# MID_AR0234.net
KiCad netlist of a schematic drawn in Altium Designer
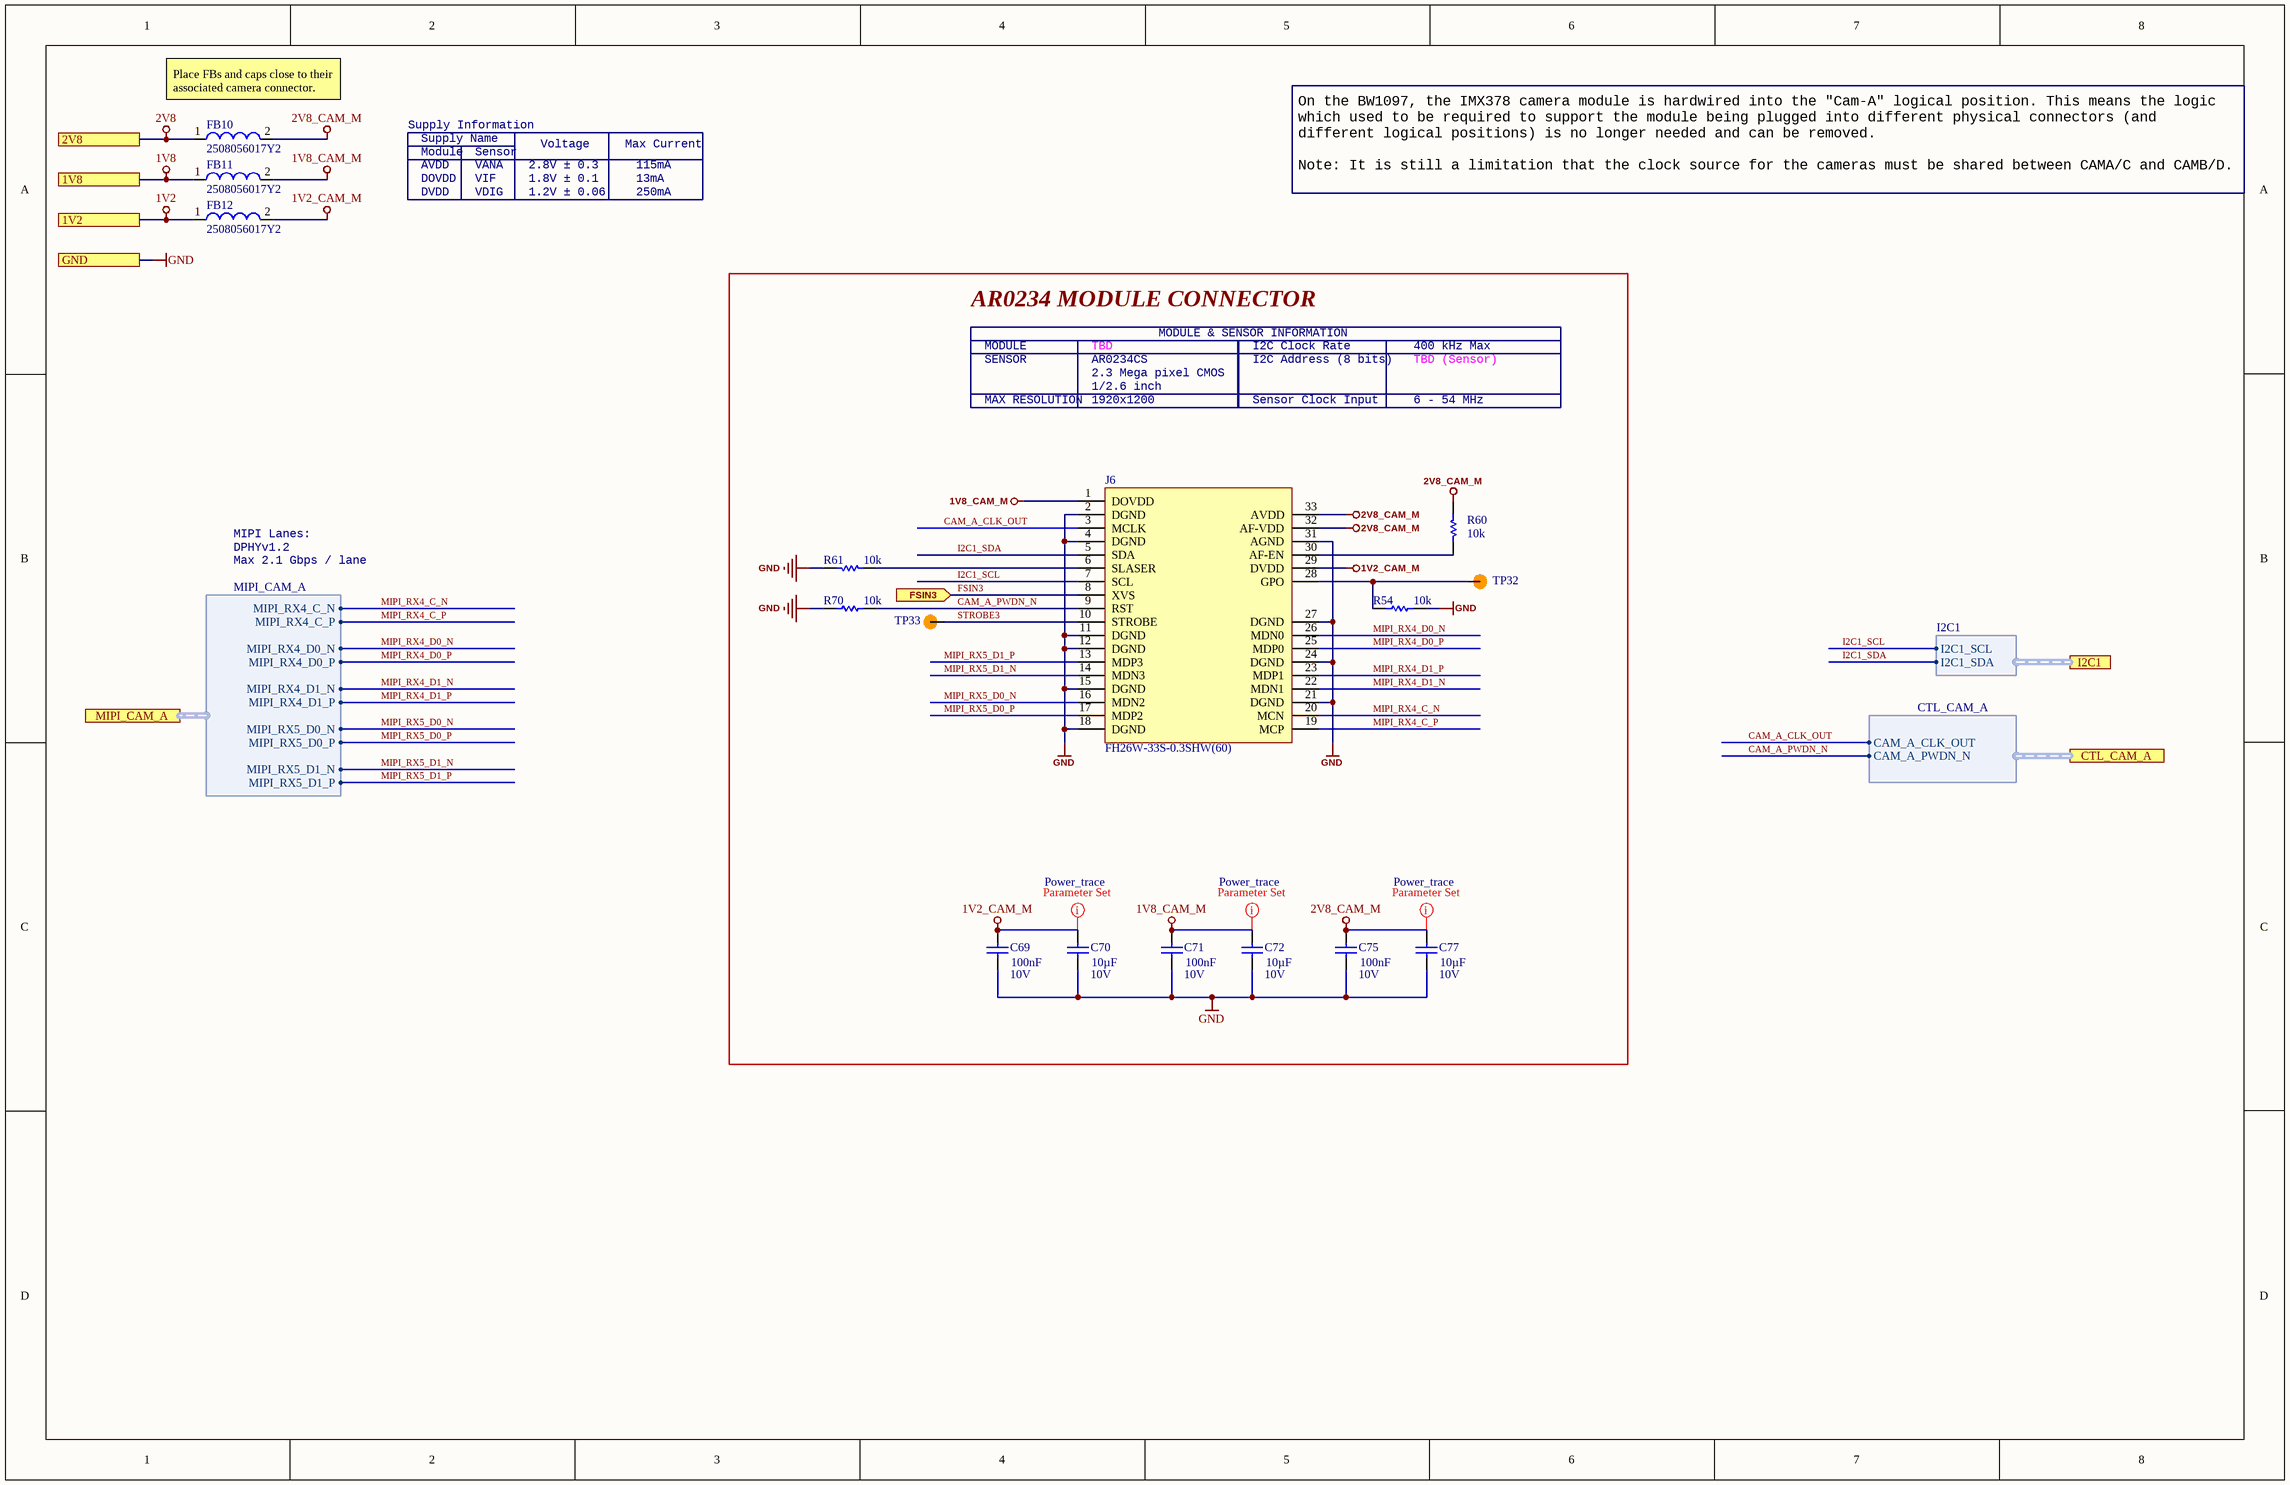
[diagram p0: MID_AR0234.SchDoc]

(export (version "E")
  (design (tool "Eeschema 10.0.6"))
  (components
    (comp (ref "C69")
      (value "100nF")
      (footprint "CAPC0402(1005)70_L")
      (description "CAP CER 0.1UF 10V X7R 0402 5%")
      (fields
        (field (name "TOLERANCE") "5%")
        (field (name "VOLTAGE RATING") "10V")
        (field (name "Comment") "GRM155R71A104JA01D")
      )
      (libsource (lib "Luxonis LLC") (part "GRM188R61C475KAAJD"))
    )
    (comp (ref "C70")
      (value "10µF")
      (footprint "CAPC0603(1608)100_L")
      (description "CAP CER 10UF 10V X5R 0603 20%")
      (fields
        (field (name "TOLERANCE") "20%")
        (field (name "VOLTAGE RATING") "10V")
        (field (name "Comment") "GRM188R61A106ME69D")
      )
      (libsource (lib "Luxonis LLC") (part "LLL153C70G474ME17E"))
    )
    (comp (ref "C71")
      (value "100nF")
      (footprint "CAPC0402(1005)70_L")
      (description "CAP CER 0.1UF 10V X7R 0402 5%")
      (fields
        (field (name "TOLERANCE") "5%")
        (field (name "VOLTAGE RATING") "10V")
        (field (name "Comment") "GRM155R71A104JA01D")
      )
      (libsource (lib "Luxonis LLC") (part "GRM188R61C475KAAJD"))
    )
    (comp (ref "C72")
      (value "10µF")
      (footprint "CAPC0603(1608)100_L")
      (description "CAP CER 10UF 10V X5R 0603 20%")
      (fields
        (field (name "TOLERANCE") "20%")
        (field (name "VOLTAGE RATING") "10V")
        (field (name "Comment") "GRM188R61A106ME69D")
      )
      (libsource (lib "Luxonis LLC") (part "LLL153C70G474ME17E"))
    )
    (comp (ref "C75")
      (value "100nF")
      (footprint "CAPC0402(1005)70_L")
      (description "CAP CER 0.1UF 10V X7R 0402 5%")
      (fields
        (field (name "TOLERANCE") "5%")
        (field (name "VOLTAGE RATING") "10V")
        (field (name "Comment") "GRM155R71A104JA01D")
      )
      (libsource (lib "Luxonis LLC") (part "GRM188R61C475KAAJD"))
    )
    (comp (ref "C77")
      (value "10µF")
      (footprint "CAPC0603(1608)100_L")
      (description "CAP CER 10UF 10V X5R 0603 20%")
      (fields
        (field (name "TOLERANCE") "20%")
        (field (name "VOLTAGE RATING") "10V")
        (field (name "Comment") "GRM188R61A106ME69D")
      )
      (libsource (lib "Luxonis LLC") (part "LLL153C70G474ME17E"))
    )
    (comp (ref "FB10")
      (value "2508056017Y2")
      (footprint "2508056017Y2")
      (description "FERRITE BEAD, 0.1OHM, 2A, 0805, 600R/100MHz")
      (fields (field (name "TOLERANCE") "25%"))
      (libsource (lib "Luxonis LLC") (part "2508056017Y2"))
    )
    (comp (ref "FB11")
      (value "2508056017Y2")
      (footprint "2508056017Y2")
      (description "FERRITE BEAD, 0.1OHM, 2A, 0805, 600R/100MHz")
      (fields (field (name "TOLERANCE") "25%"))
      (libsource (lib "Luxonis LLC") (part "2508056017Y2"))
    )
    (comp (ref "FB12")
      (value "2508056017Y2")
      (footprint "2508056017Y2")
      (description "FERRITE BEAD, 0.1OHM, 2A, 0805, 600R/100MHz")
      (fields (field (name "TOLERANCE") "25%"))
      (libsource (lib "Luxonis LLC") (part "2508056017Y2"))
    )
    (comp (ref "J6")
      (value "FH26W-33S-0.3SHW(60)")
      (footprint "FH26W-33S-0.3SHW(60)")
      (description "FFC/FPC Connector, 33 Contact(s), 1 Row(s), Female, Right Angle, Surface Mount Terminal")
      (libsource (lib "Luxonis LLC") (part "FH26W-33S-0.3SHW(60)"))
    )
    (comp (ref "R54")
      (value "10k")
      (footprint "RESC0402(1005)_L")
      (description "RES SMD 10K OHM 1% 1/16W 0402")
      (fields (field (name "TOLERANCE") "1%") (field (name "Comment") "RC0402FR-1310KL"))
      (libsource (lib "Luxonis LLC") (part "RC0402FR-0722RL_1"))
    )
    (comp (ref "R60")
      (value "10k")
      (footprint "RESC0402(1005)_L")
      (description "RES SMD 10K OHM 1% 1/16W 0402")
      (fields (field (name "TOLERANCE") "1%") (field (name "Comment") "RC0402FR-1310KL"))
      (libsource (lib "Luxonis LLC") (part "RC0402FR-0722RL_1"))
    )
    (comp (ref "R61")
      (value "10k")
      (footprint "RESC0402(1005)_L")
      (description "RES SMD 10K OHM 1% 1/16W 0402")
      (fields (field (name "TOLERANCE") "1%") (field (name "Comment") "RC0402FR-1310KL"))
      (libsource (lib "Luxonis LLC") (part "RC0402FR-0722RL_1"))
    )
    (comp (ref "R70")
      (value "10k")
      (footprint "RESC0402(1005)_L")
      (description "RES SMD 10K OHM 1% 1/16W 0402")
      (fields (field (name "TOLERANCE") "1%") (field (name "Comment") "RC0402FR-1310KL"))
      (libsource (lib "Luxonis LLC") (part "RC0402FR-0722RL_1"))
    )
    (comp (ref "TP32")
      (value "TEST_POINT")
      (footprint "TP100_200_NS")
      (libsource (lib "Luxonis LLC") (part "TEST_POINT"))
    )
    (comp (ref "TP33")
      (value "TEST_POINT")
      (footprint "TP100_200_NS")
      (libsource (lib "Luxonis LLC") (part "TEST_POINT"))
    )
  )
  (nets
    (net (code "4") (name "/CAM_A_CLK_OUT") (class "Default")
      (node (ref "J6") (pin "3") (pinfunction "MCLK_3") (pintype "passive"))
    )
    (net (code "5") (name "/CAM_A_PWDN_N") (class "Default")
      (node (ref "J6") (pin "9") (pinfunction "RST_9") (pintype "passive"))
      (node (ref "R70") (pin "2") (pinfunction "2_2") (pintype "passive"))
    )
    (net (code "6") (name "/FSIN3") (class "Default")
      (node (ref "J6") (pin "8") (pinfunction "XVS_8") (pintype "passive"))
    )
    (net (code "7") (name "/I2C1_SCL") (class "Default")
      (node (ref "J6") (pin "7") (pinfunction "SCL_7") (pintype "passive"))
    )
    (net (code "8") (name "/I2C1_SDA") (class "Default")
      (node (ref "J6") (pin "5") (pinfunction "SDA_5") (pintype "passive"))
    )
    (net (code "9") (name "/MIPI_RX4_C_N") (class "Default")
      (node (ref "J6") (pin "20") (pinfunction "MCN_20") (pintype "passive"))
    )
    (net (code "10") (name "/MIPI_RX4_C_P") (class "Default")
      (node (ref "J6") (pin "19") (pinfunction "MCP_19") (pintype "passive"))
    )
    (net (code "11") (name "/MIPI_RX4_D0_N") (class "Default")
      (node (ref "J6") (pin "26") (pinfunction "MDN0_26") (pintype "passive"))
    )
    (net (code "12") (name "/MIPI_RX4_D0_P") (class "Default")
      (node (ref "J6") (pin "25") (pinfunction "MDP0_25") (pintype "passive"))
    )
    (net (code "13") (name "/MIPI_RX4_D1_N") (class "Default")
      (node (ref "J6") (pin "22") (pinfunction "MDN1_22") (pintype "passive"))
    )
    (net (code "14") (name "/MIPI_RX4_D1_P") (class "Default")
      (node (ref "J6") (pin "23") (pinfunction "MDP1_23") (pintype "passive"))
    )
    (net (code "15") (name "/MIPI_RX5_D0_N") (class "Default")
      (node (ref "J6") (pin "16") (pinfunction "MDN2_16") (pintype "passive"))
    )
    (net (code "16") (name "/MIPI_RX5_D0_P") (class "Default")
      (node (ref "J6") (pin "17") (pinfunction "MDP2_17") (pintype "passive"))
    )
    (net (code "17") (name "/MIPI_RX5_D1_N") (class "Default")
      (node (ref "J6") (pin "14") (pinfunction "MDN3_14") (pintype "passive"))
    )
    (net (code "18") (name "/MIPI_RX5_D1_P") (class "Default")
      (node (ref "J6") (pin "13") (pinfunction "MDP3_13") (pintype "passive"))
    )
    (net (code "19") (name "/STROBE3") (class "Default")
      (node (ref "J6") (pin "10") (pinfunction "STROBE_10") (pintype "passive"))
      (node (ref "TP33") (pin "1") (pintype "passive"))
    )
    (net (code "23") (name "1V2") (class "Default")
      (node (ref "FB12") (pin "1") (pinfunction "1_1") (pintype "passive"))
    )
    (net (code "24") (name "1V2_CAM_M") (class "Default")
      (node (ref "C69") (pin "2") (pinfunction "2_2") (pintype "passive"))
      (node (ref "C70") (pin "2") (pinfunction "2_2") (pintype "passive"))
      (node (ref "FB12") (pin "2") (pinfunction "2_2") (pintype "passive"))
      (node (ref "J6") (pin "29") (pinfunction "DVDD_29") (pintype "passive"))
    )
    (net (code "25") (name "1V8") (class "Default")
      (node (ref "FB11") (pin "1") (pinfunction "1_1") (pintype "passive"))
    )
    (net (code "26") (name "1V8_CAM_M") (class "Default")
      (node (ref "C71") (pin "2") (pinfunction "2_2") (pintype "passive"))
      (node (ref "C72") (pin "2") (pinfunction "2_2") (pintype "passive"))
      (node (ref "FB11") (pin "2") (pinfunction "2_2") (pintype "passive"))
      (node (ref "J6") (pin "1") (pinfunction "DOVDD_1") (pintype "passive"))
    )
    (net (code "27") (name "2V8") (class "Default")
      (node (ref "FB10") (pin "1") (pinfunction "1_1") (pintype "passive"))
    )
    (net (code "28") (name "2V8_CAM_M") (class "Default")
      (node (ref "C75") (pin "2") (pinfunction "2_2") (pintype "passive"))
      (node (ref "C77") (pin "2") (pinfunction "2_2") (pintype "passive"))
      (node (ref "FB10") (pin "2") (pinfunction "2_2") (pintype "passive"))
      (node (ref "J6") (pin "32") (pinfunction "AF-VDD_32") (pintype "passive"))
      (node (ref "J6") (pin "33") (pinfunction "AVDD_33") (pintype "passive"))
      (node (ref "R60") (pin "1") (pinfunction "1_1") (pintype "passive"))
    )
    (net (code "29") (name "GND") (class "Default")
      (node (ref "C69") (pin "1") (pinfunction "1_1") (pintype "passive"))
      (node (ref "C70") (pin "1") (pinfunction "1_1") (pintype "passive"))
      (node (ref "C71") (pin "1") (pinfunction "1_1") (pintype "passive"))
      (node (ref "C72") (pin "1") (pinfunction "1_1") (pintype "passive"))
      (node (ref "C75") (pin "1") (pinfunction "1_1") (pintype "passive"))
      (node (ref "C77") (pin "1") (pinfunction "1_1") (pintype "passive"))
      (node (ref "J6") (pin "11") (pinfunction "DGND_11") (pintype "passive"))
      (node (ref "J6") (pin "12") (pinfunction "DGND_12") (pintype "passive"))
      (node (ref "J6") (pin "15") (pinfunction "DGND_15") (pintype "passive"))
      (node (ref "J6") (pin "18") (pinfunction "DGND_18") (pintype "passive"))
      (node (ref "J6") (pin "2") (pinfunction "DGND_2") (pintype "passive"))
      (node (ref "J6") (pin "21") (pinfunction "DGND_21") (pintype "passive"))
      (node (ref "J6") (pin "24") (pinfunction "DGND_24") (pintype "passive"))
      (node (ref "J6") (pin "27") (pinfunction "DGND_27") (pintype "passive"))
      (node (ref "J6") (pin "31") (pinfunction "AGND_31") (pintype "passive"))
      (node (ref "J6") (pin "4") (pinfunction "DGND_4") (pintype "passive"))
      (node (ref "R54") (pin "2") (pinfunction "2_2") (pintype "passive"))
      (node (ref "R61") (pin "2") (pinfunction "2_2") (pintype "passive"))
      (node (ref "R70") (pin "1") (pinfunction "1_1") (pintype "passive"))
    )
    (net (code "30") (name "Net-(J6-AF-EN)") (class "Default")
      (node (ref "J6") (pin "30") (pinfunction "AF-EN_30") (pintype "passive"))
      (node (ref "R60") (pin "2") (pinfunction "2_2") (pintype "passive"))
    )
    (net (code "31") (name "Net-(J6-GPO)") (class "Default")
      (node (ref "J6") (pin "28") (pinfunction "GPO_28") (pintype "passive"))
      (node (ref "R54") (pin "1") (pinfunction "1_1") (pintype "passive"))
      (node (ref "TP32") (pin "1") (pintype "passive"))
    )
    (net (code "32") (name "Net-(J6-SLASER)") (class "Default")
      (node (ref "J6") (pin "6") (pinfunction "SLASER_6") (pintype "passive"))
      (node (ref "R61") (pin "1") (pinfunction "1_1") (pintype "passive"))
    )
  )
)
